# Schematic.net
KiCad netlist of a schematic drawn in EAGLE
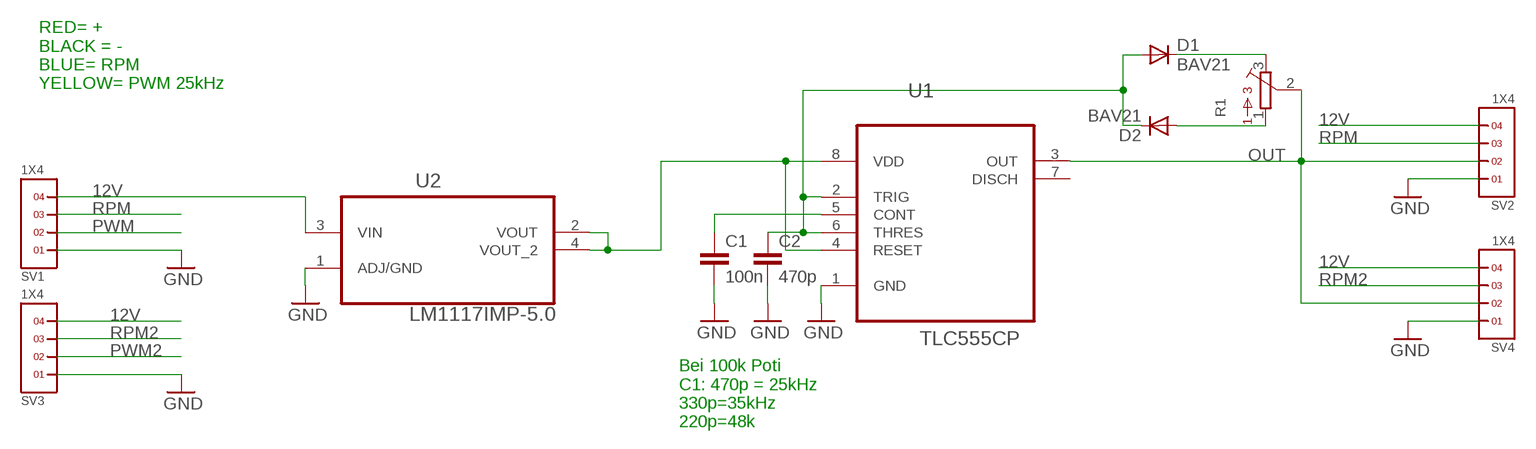
[diagram p0: schematic, sheet 1]

(export (version "E")
  (design (tool "Eeschema 10.0.6"))
  (components
    (comp (ref "C1")
      (value "100n")
      (footprint "eagle-import:C025-025X050")
      (libsource (lib "eagle-import") (part "C-EU025-025X050"))
    )
    (comp (ref "C2")
      (value "470p")
      (footprint "eagle-import:C025-025X050")
      (libsource (lib "eagle-import") (part "C-EU025-025X050"))
    )
    (comp (ref "D1")
      (value "BAV21")
      (footprint "eagle-import:DO35-10")
      (libsource (lib "eagle-import") (part "BAV21"))
    )
    (comp (ref "D2")
      (value "BAV21")
      (footprint "eagle-import:DO35-10")
      (libsource (lib "eagle-import") (part "BAV21"))
    )
    (comp (ref "R1")
      (value "3362P")
      (footprint "eagle-import:3362P")
      (libsource (lib "eagle-import") (part "3362P"))
    )
    (comp (ref "SV1")
      (value "1X4")
      (footprint "eagle-import:1X4")
      (libsource (lib "eagle-import") (part "1X4"))
    )
    (comp (ref "SV2")
      (value "1X4")
      (footprint "eagle-import:1X4")
      (libsource (lib "eagle-import") (part "1X4"))
    )
    (comp (ref "SV3")
      (value "1X4")
      (footprint "eagle-import:1X4")
      (libsource (lib "eagle-import") (part "1X4"))
    )
    (comp (ref "SV4")
      (value "1X4")
      (footprint "eagle-import:1X4")
      (libsource (lib "eagle-import") (part "1X4"))
    )
    (comp (ref "U1")
      (value "TLC555CP")
      (footprint "eagle-import:DIP254P762X508-8")
      (libsource (lib "eagle-import") (part "TLC555CP"))
    )
    (comp (ref "U2")
      (value "LM1117IMP-5.0")
      (footprint "eagle-import:SOT230P696X180-4N")
      (libsource (lib "eagle-import") (part "LM1117IMP-5.0"))
    )
  )
  (nets
    (net (code "1") (name "/12V") (class "Default")
      (node (ref "SV1") (pin "4") (pinfunction "4_4") (pintype "bidirectional"))
      (node (ref "SV2") (pin "4") (pinfunction "4_4") (pintype "bidirectional"))
      (node (ref "SV3") (pin "4") (pinfunction "4_4") (pintype "bidirectional"))
      (node (ref "SV4") (pin "4") (pinfunction "4_4") (pintype "bidirectional"))
      (node (ref "U2") (pin "3") (pinfunction "VIN_3") (pintype "input"))
    )
    (net (code "2") (name "/OUT") (class "Default")
      (node (ref "R1") (pin "2") (pinfunction "2_2") (pintype "passive"))
      (node (ref "SV2") (pin "2") (pinfunction "2_2") (pintype "bidirectional"))
      (node (ref "SV4") (pin "2") (pinfunction "2_2") (pintype "bidirectional"))
      (node (ref "U1") (pin "3") (pinfunction "OUT_3") (pintype "output"))
    )
    (net (code "3") (name "/PWM") (class "Default")
      (node (ref "SV1") (pin "2") (pinfunction "2_2") (pintype "bidirectional"))
    )
    (net (code "4") (name "/PWM2") (class "Default")
      (node (ref "SV3") (pin "2") (pinfunction "2_2") (pintype "bidirectional"))
    )
    (net (code "5") (name "/RPM") (class "Default")
      (node (ref "SV1") (pin "3") (pinfunction "3_3") (pintype "bidirectional"))
      (node (ref "SV2") (pin "3") (pinfunction "3_3") (pintype "bidirectional"))
    )
    (net (code "6") (name "/RPM2") (class "Default")
      (node (ref "SV3") (pin "3") (pinfunction "3_3") (pintype "bidirectional"))
      (node (ref "SV4") (pin "3") (pinfunction "3_3") (pintype "bidirectional"))
    )
    (net (code "7") (name "GND") (class "Default")
      (node (ref "C1") (pin "2") (pinfunction "2_2") (pintype "passive"))
      (node (ref "C2") (pin "2") (pinfunction "2_2") (pintype "passive"))
      (node (ref "SV1") (pin "1") (pinfunction "1_1") (pintype "bidirectional"))
      (node (ref "SV2") (pin "1") (pinfunction "1_1") (pintype "bidirectional"))
      (node (ref "SV3") (pin "1") (pinfunction "1_1") (pintype "bidirectional"))
      (node (ref "SV4") (pin "1") (pinfunction "1_1") (pintype "bidirectional"))
      (node (ref "U1") (pin "1") (pinfunction "GND_1") (pintype "passive"))
      (node (ref "U2") (pin "1") (pinfunction "ADJ/GND_1") (pintype "passive"))
    )
    (net (code "8") (name "Net-(D1-PadC)") (class "Default")
      (node (ref "D1") (pin "C") (pinfunction "C_C") (pintype "passive"))
      (node (ref "R1") (pin "3") (pinfunction "3_3") (pintype "passive"))
    )
    (net (code "9") (name "Net-(D2-PadA)") (class "Default")
      (node (ref "D2") (pin "A") (pinfunction "A_A") (pintype "passive"))
      (node (ref "R1") (pin "1") (pinfunction "1_1") (pintype "passive"))
    )
    (net (code "10") (name "Net-(U1-CONT)") (class "Default")
      (node (ref "C1") (pin "1") (pinfunction "1_1") (pintype "passive"))
      (node (ref "U1") (pin "5") (pinfunction "CONT_5") (pintype "input"))
    )
    (net (code "11") (name "Net-(U1-RESET)") (class "Default")
      (node (ref "U1") (pin "4") (pinfunction "RESET_4") (pintype "input"))
      (node (ref "U1") (pin "8") (pinfunction "VDD_8") (pintype "power_in"))
      (node (ref "U2") (pin "2") (pinfunction "VOUT_2") (pintype "output"))
      (node (ref "U2") (pin "4") (pinfunction "VOUT_2_4") (pintype "output"))
    )
    (net (code "12") (name "Net-(U1-THRES)") (class "Default")
      (node (ref "C2") (pin "1") (pinfunction "1_1") (pintype "passive"))
      (node (ref "D1") (pin "A") (pinfunction "A_A") (pintype "passive"))
      (node (ref "D2") (pin "C") (pinfunction "C_C") (pintype "passive"))
      (node (ref "U1") (pin "2") (pinfunction "TRIG_2") (pintype "input"))
      (node (ref "U1") (pin "6") (pinfunction "THRES_6") (pintype "input"))
    )
    (net (code "13") (name "unconnected-(U1-DISCH-Pad7)") (class "Default")
      (node (ref "U1") (pin "7") (pinfunction "DISCH_7") (pintype "output"))
    )
  )
)
